# wifi-ra02.net
KiCad netlist of a schematic drawn in EasyEDA
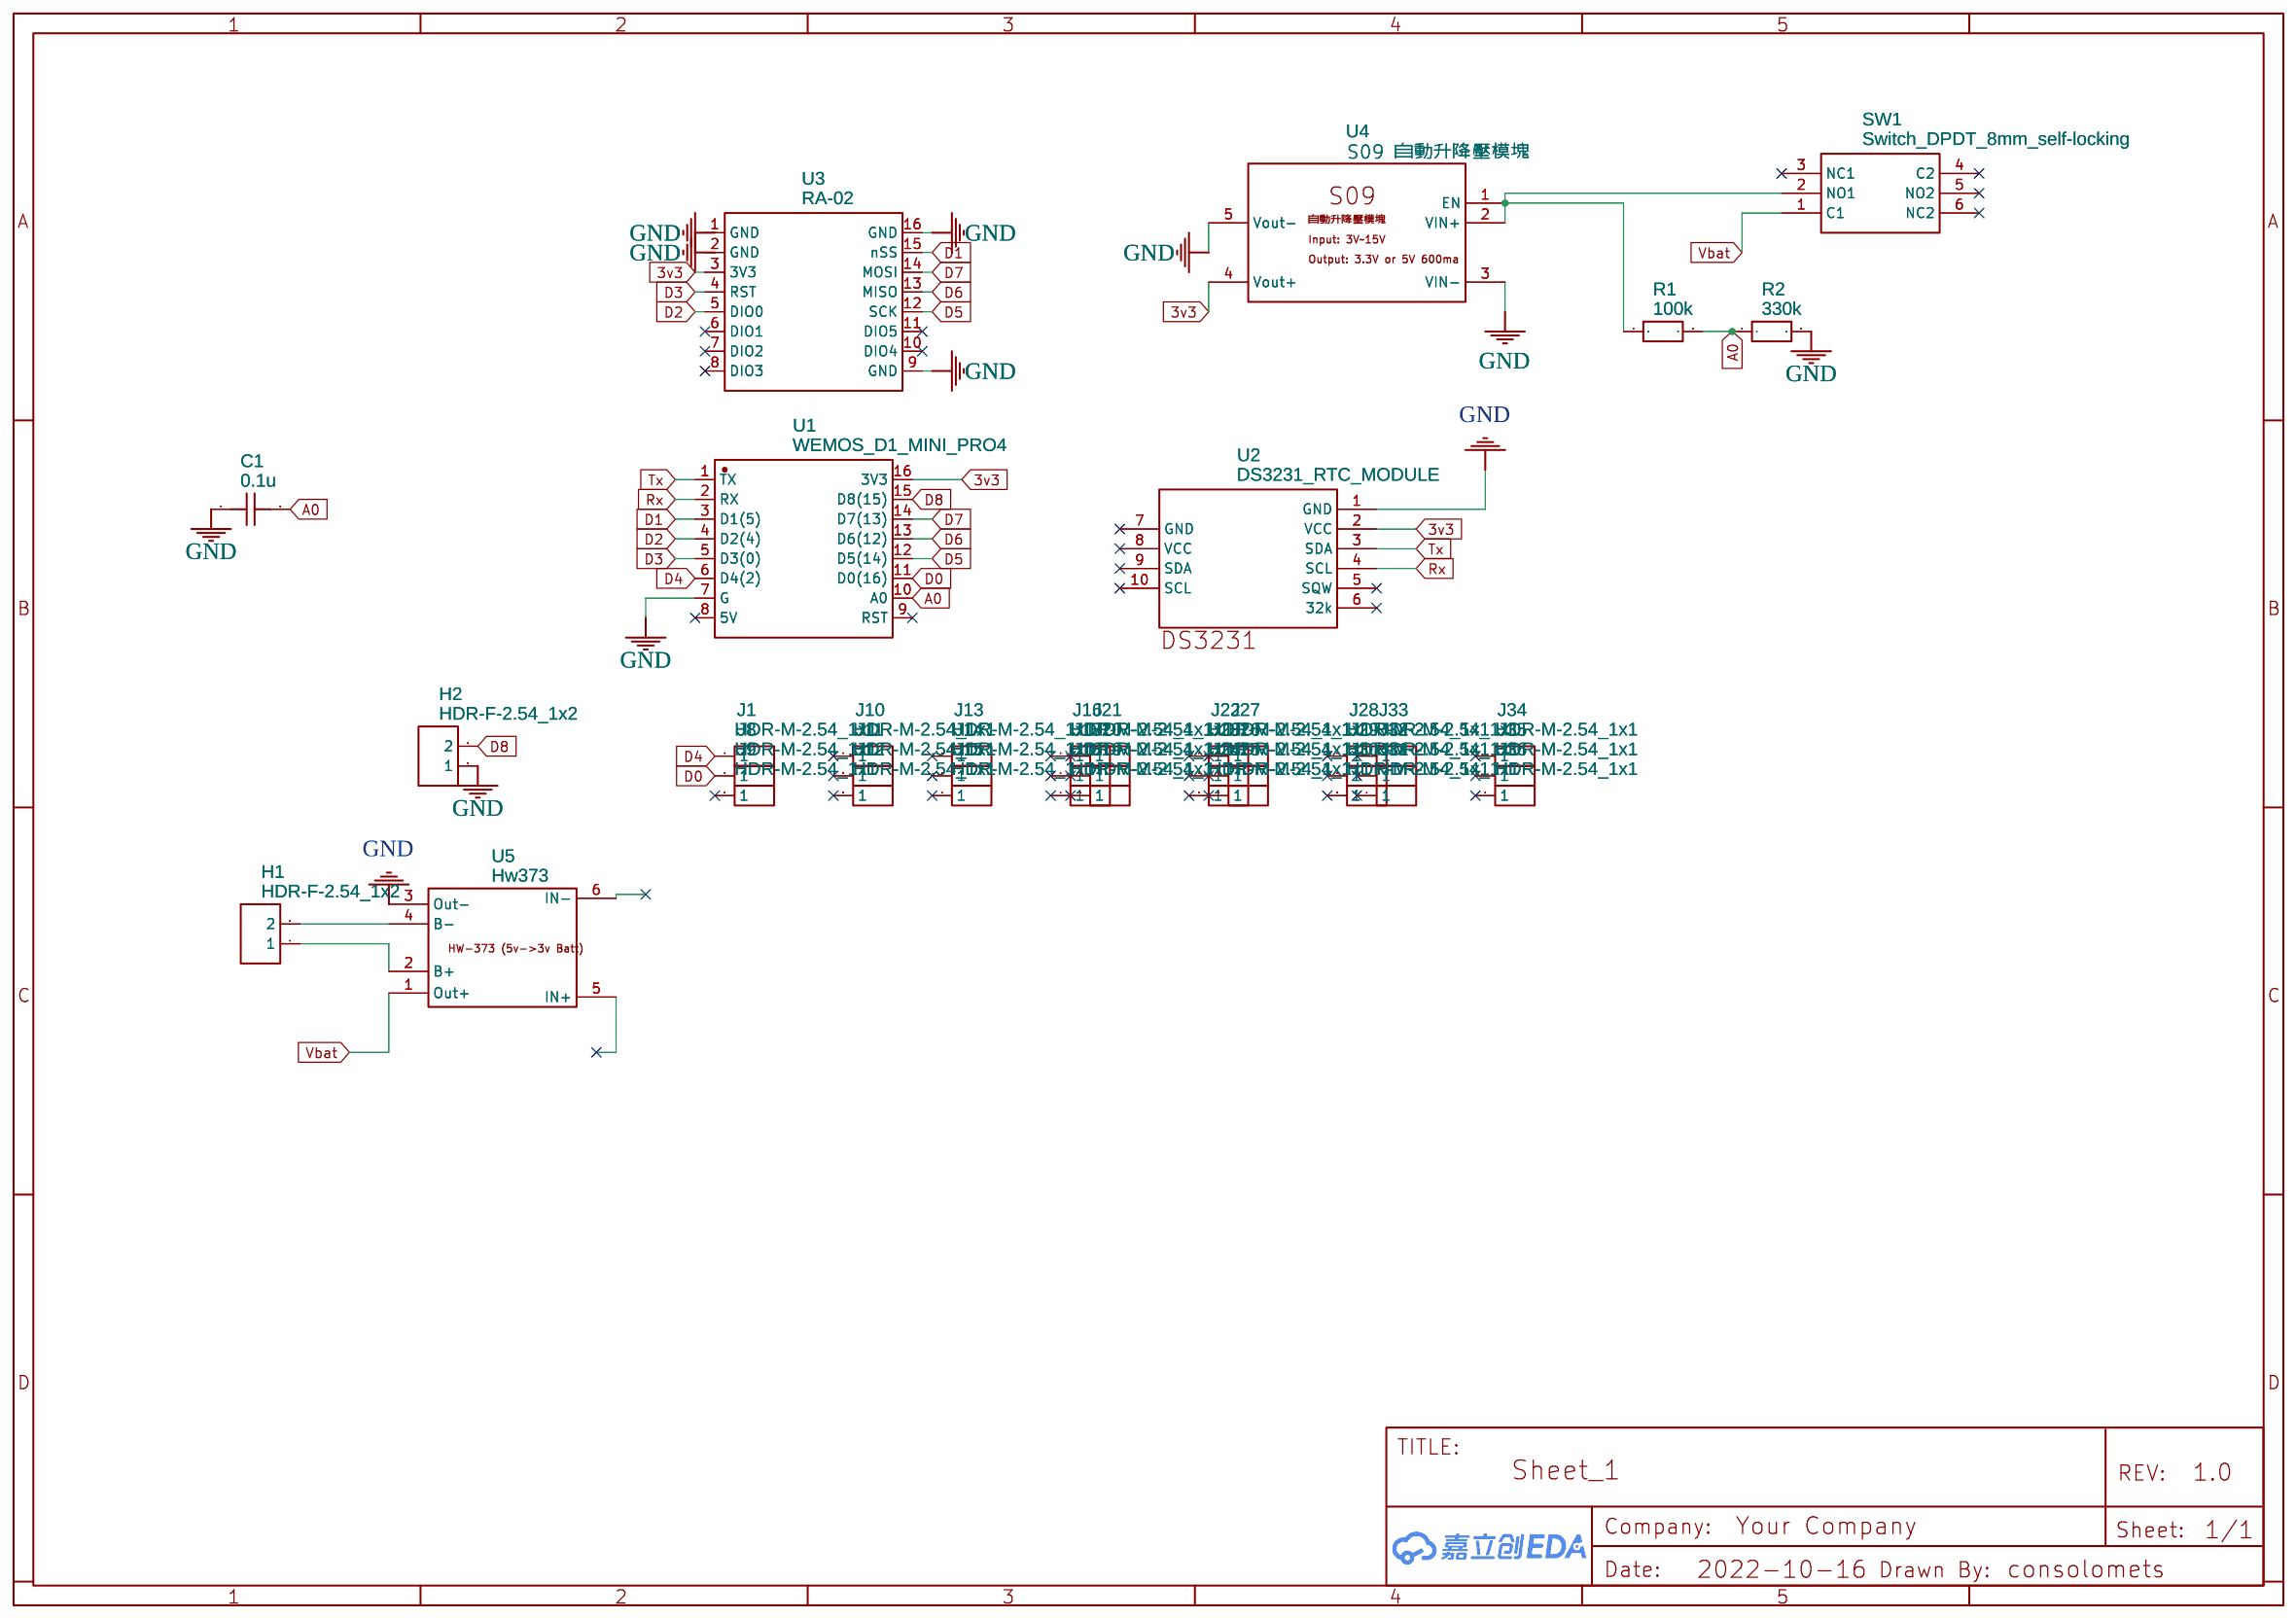
[diagram p0: schematic sheet]

(export (version "E")
  (design (tool "Eeschema 10.0.6"))
  (components
    (comp (ref "C1") (value "0.1u") (libsource (lib "") (part "C_0603_US")))
    (comp (ref "H1")
      (value "HDR-F-2.54_1x2")
      (fields (field (name "BOM_Supplier Part") "C49661"))
      (libsource (lib "") (part "HDR-F-2.54_1x2"))
    )
    (comp (ref "H2")
      (value "HDR-F-2.54_1x2")
      (fields (field (name "BOM_Supplier Part") "C49661"))
      (libsource (lib "") (part "HDR-F-2.54_1x2"))
    )
    (comp (ref "J1")
      (value "HDR-M-2.54_1x1")
      (fields (field (name "BOM_Supplier Part") "C81276"))
      (libsource (lib "") (part "HDR-M-2.54_1x1"))
    )
    (comp (ref "J8")
      (value "HDR-M-2.54_1x1")
      (fields (field (name "BOM_Supplier Part") "C81276"))
      (libsource (lib "") (part "HDR-M-2.54_1x1"))
    )
    (comp (ref "J9")
      (value "HDR-M-2.54_1x1")
      (fields (field (name "BOM_Supplier Part") "C81276"))
      (libsource (lib "") (part "HDR-M-2.54_1x1"))
    )
    (comp (ref "J10")
      (value "HDR-M-2.54_1x1")
      (fields (field (name "BOM_Supplier Part") "C81276"))
      (libsource (lib "") (part "HDR-M-2.54_1x1"))
    )
    (comp (ref "J11")
      (value "HDR-M-2.54_1x1")
      (fields (field (name "BOM_Supplier Part") "C81276"))
      (libsource (lib "") (part "HDR-M-2.54_1x1"))
    )
    (comp (ref "J12")
      (value "HDR-M-2.54_1x1")
      (fields (field (name "BOM_Supplier Part") "C81276"))
      (libsource (lib "") (part "HDR-M-2.54_1x1"))
    )
    (comp (ref "J13")
      (value "HDR-M-2.54_1x1")
      (fields (field (name "BOM_Supplier Part") "C81276"))
      (libsource (lib "") (part "HDR-M-2.54_1x1"))
    )
    (comp (ref "J14")
      (value "HDR-M-2.54_1x1")
      (fields (field (name "BOM_Supplier Part") "C81276"))
      (libsource (lib "") (part "HDR-M-2.54_1x1"))
    )
    (comp (ref "J15")
      (value "HDR-M-2.54_1x1")
      (fields (field (name "BOM_Supplier Part") "C81276"))
      (libsource (lib "") (part "HDR-M-2.54_1x1"))
    )
    (comp (ref "J16")
      (value "HDR-M-2.54_1x1")
      (fields (field (name "BOM_Supplier Part") "C81276"))
      (libsource (lib "") (part "HDR-M-2.54_1x1"))
    )
    (comp (ref "J17")
      (value "HDR-M-2.54_1x1")
      (fields (field (name "BOM_Supplier Part") "C81276"))
      (libsource (lib "") (part "HDR-M-2.54_1x1"))
    )
    (comp (ref "J18")
      (value "HDR-M-2.54_1x1")
      (fields (field (name "BOM_Supplier Part") "C81276"))
      (libsource (lib "") (part "HDR-M-2.54_1x1"))
    )
    (comp (ref "J19")
      (value "HDR-M-2.54_1x1")
      (fields (field (name "BOM_Supplier Part") "C81276"))
      (libsource (lib "") (part "HDR-M-2.54_1x1"))
    )
    (comp (ref "J20")
      (value "HDR-M-2.54_1x1")
      (fields (field (name "BOM_Supplier Part") "C81276"))
      (libsource (lib "") (part "HDR-M-2.54_1x1"))
    )
    (comp (ref "J21")
      (value "HDR-M-2.54_1x1")
      (fields (field (name "BOM_Supplier Part") "C81276"))
      (libsource (lib "") (part "HDR-M-2.54_1x1"))
    )
    (comp (ref "J22")
      (value "HDR-M-2.54_1x1")
      (fields (field (name "BOM_Supplier Part") "C81276"))
      (libsource (lib "") (part "HDR-M-2.54_1x1"))
    )
    (comp (ref "J23")
      (value "HDR-M-2.54_1x1")
      (fields (field (name "BOM_Supplier Part") "C81276"))
      (libsource (lib "") (part "HDR-M-2.54_1x1"))
    )
    (comp (ref "J24")
      (value "HDR-M-2.54_1x1")
      (fields (field (name "BOM_Supplier Part") "C81276"))
      (libsource (lib "") (part "HDR-M-2.54_1x1"))
    )
    (comp (ref "J25")
      (value "HDR-M-2.54_1x1")
      (fields (field (name "BOM_Supplier Part") "C81276"))
      (libsource (lib "") (part "HDR-M-2.54_1x1"))
    )
    (comp (ref "J26")
      (value "HDR-M-2.54_1x1")
      (fields (field (name "BOM_Supplier Part") "C81276"))
      (libsource (lib "") (part "HDR-M-2.54_1x1"))
    )
    (comp (ref "J27")
      (value "HDR-M-2.54_1x1")
      (fields (field (name "BOM_Supplier Part") "C81276"))
      (libsource (lib "") (part "HDR-M-2.54_1x1"))
    )
    (comp (ref "J28")
      (value "HDR-M-2.54_1x1")
      (fields (field (name "BOM_Supplier Part") "C81276"))
      (libsource (lib "") (part "HDR-M-2.54_1x1"))
    )
    (comp (ref "J29")
      (value "HDR-M-2.54_1x1")
      (fields (field (name "BOM_Supplier Part") "C81276"))
      (libsource (lib "") (part "HDR-M-2.54_1x1"))
    )
    (comp (ref "J30")
      (value "HDR-M-2.54_1x1")
      (fields (field (name "BOM_Supplier Part") "C81276"))
      (libsource (lib "") (part "HDR-M-2.54_1x1"))
    )
    (comp (ref "J31")
      (value "HDR-M-2.54_1x1")
      (fields (field (name "BOM_Supplier Part") "C81276"))
      (libsource (lib "") (part "HDR-M-2.54_1x1"))
    )
    (comp (ref "J32")
      (value "HDR-M-2.54_1x1")
      (fields (field (name "BOM_Supplier Part") "C81276"))
      (libsource (lib "") (part "HDR-M-2.54_1x1"))
    )
    (comp (ref "J33")
      (value "HDR-M-2.54_1x1")
      (fields (field (name "BOM_Supplier Part") "C81276"))
      (libsource (lib "") (part "HDR-M-2.54_1x1"))
    )
    (comp (ref "J34")
      (value "HDR-M-2.54_1x1")
      (fields (field (name "BOM_Supplier Part") "C81276"))
      (libsource (lib "") (part "HDR-M-2.54_1x1"))
    )
    (comp (ref "J35")
      (value "HDR-M-2.54_1x1")
      (fields (field (name "BOM_Supplier Part") "C81276"))
      (libsource (lib "") (part "HDR-M-2.54_1x1"))
    )
    (comp (ref "J36")
      (value "HDR-M-2.54_1x1")
      (fields (field (name "BOM_Supplier Part") "C81276"))
      (libsource (lib "") (part "HDR-M-2.54_1x1"))
    )
    (comp (ref "R1") (value "100k") (libsource (lib "") (part "R_0603_EU")))
    (comp (ref "R2") (value "330k") (libsource (lib "") (part "R_0603_EU")))
    (comp (ref "SW1")
      (value "Switch_DPDT_8mm_self-locking")
      (libsource (lib "") (part "Switch_DPDT_8mm_self-locking"))
    )
    (comp (ref "U1")
      (value "WEMOS_D1_MINI_PRO4")
      (fields
        (field (name "BOM_Manufacturer Part") "Wemos_D1_mini_Pro4")
        (field (name "BOM_Supplier Part") "C2837266")
      )
      (libsource (lib "") (part "WEMOS_D1_MINI_PRO4"))
    )
    (comp (ref "U2")
      (value "DS3231_RTC_MODULE")
      (fields (field (name "BOM_Manufacturer Part") "DS3231"))
      (libsource (lib "") (part "DS3231_RTC_MODULE"))
    )
    (comp (ref "U3") (value "RA-02") (libsource (lib "") (part "RA-02")))
    (comp (ref "U4")
      (value "S09 自動升降壓模塊")
      (fields (field (name "BOM_Manufacturer Part") "S09"))
      (libsource (lib "") (part "S09 自動升降壓模塊"))
    )
    (comp (ref "U5")
      (value "Hw373")
      (fields (field (name "BOM_Manufacturer Part") "HW-373"))
      (libsource (lib "") (part "Hw373"))
    )
  )
  (nets
    (net (code "1") (name "3v3") (class "Default")
      (node (ref "U1") (pin "16") (pinfunction "3V3_16") (pintype "unspecified"))
      (node (ref "U2") (pin "2") (pinfunction "VCC_2") (pintype "unspecified"))
      (node (ref "U3") (pin "3") (pinfunction "3V3_3") (pintype "unspecified"))
      (node (ref "U4") (pin "4") (pinfunction "Vout+_4") (pintype "output"))
    )
    (net (code "2") (name "A0") (class "Default")
      (node (ref "C1") (pin "2") (pinfunction "2_2") (pintype "unspecified"))
      (node (ref "R1") (pin "2") (pinfunction "2_2") (pintype "unspecified"))
      (node (ref "R2") (pin "1") (pinfunction "1_1") (pintype "unspecified"))
      (node (ref "U1") (pin "10") (pinfunction "A0_10") (pintype "unspecified"))
    )
    (net (code "3") (name "D0") (class "Default")
      (node (ref "J8") (pin "1") (pinfunction "1_1") (pintype "input"))
      (node (ref "U1") (pin "11") (pinfunction "D0(16)_11") (pintype "unspecified"))
    )
    (net (code "4") (name "D1") (class "Default")
      (node (ref "U1") (pin "3") (pinfunction "D1(5)_3") (pintype "unspecified"))
      (node (ref "U3") (pin "15") (pinfunction "nSS_15") (pintype "unspecified"))
    )
    (net (code "5") (name "D2") (class "Default")
      (node (ref "U1") (pin "4") (pinfunction "D2(4)_4") (pintype "unspecified"))
      (node (ref "U3") (pin "5") (pinfunction "DIO0_5") (pintype "unspecified"))
    )
    (net (code "6") (name "D3") (class "Default")
      (node (ref "U1") (pin "5") (pinfunction "D3(0)_5") (pintype "unspecified"))
      (node (ref "U3") (pin "4") (pinfunction "RST_4") (pintype "unspecified"))
    )
    (net (code "7") (name "D4") (class "Default")
      (node (ref "J1") (pin "1") (pinfunction "1_1") (pintype "input"))
      (node (ref "U1") (pin "6") (pinfunction "D4(2)_6") (pintype "unspecified"))
    )
    (net (code "8") (name "D5") (class "Default")
      (node (ref "U1") (pin "12") (pinfunction "D5(14)_12") (pintype "unspecified"))
      (node (ref "U3") (pin "12") (pinfunction "SCK_12") (pintype "unspecified"))
    )
    (net (code "9") (name "D6") (class "Default")
      (node (ref "U1") (pin "13") (pinfunction "D6(12)_13") (pintype "unspecified"))
      (node (ref "U3") (pin "13") (pinfunction "MISO_13") (pintype "unspecified"))
    )
    (net (code "10") (name "D7") (class "Default")
      (node (ref "U1") (pin "14") (pinfunction "D7(13)_14") (pintype "unspecified"))
      (node (ref "U3") (pin "14") (pinfunction "MOSI_14") (pintype "unspecified"))
    )
    (net (code "11") (name "D8") (class "Default")
      (node (ref "H2") (pin "2") (pinfunction "2_2") (pintype "input"))
      (node (ref "U1") (pin "15") (pinfunction "D8(15)_15") (pintype "unspecified"))
    )
    (net (code "12") (name "GND") (class "Default")
      (node (ref "C1") (pin "1") (pinfunction "1_1") (pintype "unspecified"))
      (node (ref "H2") (pin "1") (pinfunction "1_1") (pintype "input"))
      (node (ref "R2") (pin "2") (pinfunction "2_2") (pintype "unspecified"))
      (node (ref "U1") (pin "7") (pinfunction "G_7") (pintype "unspecified"))
      (node (ref "U2") (pin "1") (pinfunction "GND_1") (pintype "unspecified"))
      (node (ref "U3") (pin "1") (pinfunction "GND_1") (pintype "unspecified"))
      (node (ref "U3") (pin "16") (pinfunction "GND_16") (pintype "unspecified"))
      (node (ref "U3") (pin "2") (pinfunction "GND_2") (pintype "unspecified"))
      (node (ref "U3") (pin "9") (pinfunction "GND_9") (pintype "unspecified"))
      (node (ref "U4") (pin "3") (pinfunction "VIN-_3") (pintype "passive"))
      (node (ref "U4") (pin "5") (pinfunction "Vout-_5") (pintype "output"))
      (node (ref "U5") (pin "3") (pinfunction "Out-_3") (pintype "unspecified"))
    )
    (net (code "13") (name "Net-(SW1-NO1)") (class "Default")
      (node (ref "R1") (pin "1") (pinfunction "1_1") (pintype "unspecified"))
      (node (ref "SW1") (pin "2") (pinfunction "NO1_2") (pintype "unspecified"))
      (node (ref "U4") (pin "1") (pinfunction "EN_1") (pintype "input"))
      (node (ref "U4") (pin "2") (pinfunction "VIN+_2") (pintype "passive"))
    )
    (net (code "14") (name "Net-(U5-B+)") (class "Default")
      (node (ref "H1") (pin "1") (pinfunction "1_1") (pintype "input"))
      (node (ref "U5") (pin "2") (pinfunction "B+_2") (pintype "passive"))
    )
    (net (code "15") (name "Net-(U5-B-)") (class "Default")
      (node (ref "H1") (pin "2") (pinfunction "2_2") (pintype "input"))
      (node (ref "U5") (pin "4") (pinfunction "B-_4") (pintype "unspecified"))
    )
    (net (code "16") (name "Rx") (class "Default")
      (node (ref "U1") (pin "2") (pinfunction "RX_2") (pintype "unspecified"))
      (node (ref "U2") (pin "4") (pinfunction "SCL_4") (pintype "unspecified"))
    )
    (net (code "17") (name "Tx") (class "Default")
      (node (ref "U1") (pin "1") (pinfunction "TX_1") (pintype "unspecified"))
      (node (ref "U2") (pin "3") (pinfunction "SDA_3") (pintype "unspecified"))
    )
    (net (code "18") (name "Vbat") (class "Default")
      (node (ref "SW1") (pin "1") (pinfunction "C1_1") (pintype "unspecified"))
      (node (ref "U5") (pin "1") (pinfunction "Out+_1") (pintype "output"))
    )
    (net (code "19") (name "unconnected-(J9-Pad1)") (class "Default")
      (node (ref "J9") (pin "1") (pinfunction "1_1") (pintype "input+no_connect"))
    )
    (net (code "20") (name "unconnected-(J10-Pad1)") (class "Default")
      (node (ref "J10") (pin "1") (pinfunction "1_1") (pintype "input+no_connect"))
    )
    (net (code "21") (name "unconnected-(J11-Pad1)") (class "Default")
      (node (ref "J11") (pin "1") (pinfunction "1_1") (pintype "input+no_connect"))
    )
    (net (code "22") (name "unconnected-(J12-Pad1)") (class "Default")
      (node (ref "J12") (pin "1") (pinfunction "1_1") (pintype "input+no_connect"))
    )
    (net (code "23") (name "unconnected-(J13-Pad1)") (class "Default")
      (node (ref "J13") (pin "1") (pinfunction "1_1") (pintype "input+no_connect"))
    )
    (net (code "24") (name "unconnected-(J14-Pad1)") (class "Default")
      (node (ref "J14") (pin "1") (pinfunction "1_1") (pintype "input+no_connect"))
    )
    (net (code "25") (name "unconnected-(J15-Pad1)") (class "Default")
      (node (ref "J15") (pin "1") (pinfunction "1_1") (pintype "input+no_connect"))
    )
    (net (code "26") (name "unconnected-(J16-Pad1)") (class "Default")
      (node (ref "J16") (pin "1") (pinfunction "1_1") (pintype "input+no_connect"))
    )
    (net (code "27") (name "unconnected-(J17-Pad1)") (class "Default")
      (node (ref "J17") (pin "1") (pinfunction "1_1") (pintype "input+no_connect"))
    )
    (net (code "28") (name "unconnected-(J18-Pad1)") (class "Default")
      (node (ref "J18") (pin "1") (pinfunction "1_1") (pintype "input+no_connect"))
    )
    (net (code "29") (name "unconnected-(J19-Pad1)") (class "Default")
      (node (ref "J19") (pin "1") (pinfunction "1_1") (pintype "input+no_connect"))
    )
    (net (code "30") (name "unconnected-(J20-Pad1)") (class "Default")
      (node (ref "J20") (pin "1") (pinfunction "1_1") (pintype "input+no_connect"))
    )
    (net (code "31") (name "unconnected-(J21-Pad1)") (class "Default")
      (node (ref "J21") (pin "1") (pinfunction "1_1") (pintype "input+no_connect"))
    )
    (net (code "32") (name "unconnected-(J22-Pad1)") (class "Default")
      (node (ref "J22") (pin "1") (pinfunction "1_1") (pintype "input+no_connect"))
    )
    (net (code "33") (name "unconnected-(J23-Pad1)") (class "Default")
      (node (ref "J23") (pin "1") (pinfunction "1_1") (pintype "input+no_connect"))
    )
    (net (code "34") (name "unconnected-(J24-Pad1)") (class "Default")
      (node (ref "J24") (pin "1") (pinfunction "1_1") (pintype "input+no_connect"))
    )
    (net (code "35") (name "unconnected-(J25-Pad1)") (class "Default")
      (node (ref "J25") (pin "1") (pinfunction "1_1") (pintype "input+no_connect"))
    )
    (net (code "36") (name "unconnected-(J26-Pad1)") (class "Default")
      (node (ref "J26") (pin "1") (pinfunction "1_1") (pintype "input+no_connect"))
    )
    (net (code "37") (name "unconnected-(J27-Pad1)") (class "Default")
      (node (ref "J27") (pin "1") (pinfunction "1_1") (pintype "input+no_connect"))
    )
    (net (code "38") (name "unconnected-(J28-Pad1)") (class "Default")
      (node (ref "J28") (pin "1") (pinfunction "1_1") (pintype "input+no_connect"))
    )
    (net (code "39") (name "unconnected-(J29-Pad1)") (class "Default")
      (node (ref "J29") (pin "1") (pinfunction "1_1") (pintype "input+no_connect"))
    )
    (net (code "40") (name "unconnected-(J30-Pad1)") (class "Default")
      (node (ref "J30") (pin "1") (pinfunction "1_1") (pintype "input+no_connect"))
    )
    (net (code "41") (name "unconnected-(J31-Pad1)") (class "Default")
      (node (ref "J31") (pin "1") (pinfunction "1_1") (pintype "input+no_connect"))
    )
    (net (code "42") (name "unconnected-(J32-Pad1)") (class "Default")
      (node (ref "J32") (pin "1") (pinfunction "1_1") (pintype "input+no_connect"))
    )
    (net (code "43") (name "unconnected-(J33-Pad1)") (class "Default")
      (node (ref "J33") (pin "1") (pinfunction "1_1") (pintype "input+no_connect"))
    )
    (net (code "44") (name "unconnected-(J34-Pad1)") (class "Default")
      (node (ref "J34") (pin "1") (pinfunction "1_1") (pintype "input+no_connect"))
    )
    (net (code "45") (name "unconnected-(J35-Pad1)") (class "Default")
      (node (ref "J35") (pin "1") (pinfunction "1_1") (pintype "input+no_connect"))
    )
    (net (code "46") (name "unconnected-(J36-Pad1)") (class "Default")
      (node (ref "J36") (pin "1") (pinfunction "1_1") (pintype "input+no_connect"))
    )
    (net (code "47") (name "unconnected-(SW1-C2-Pad4)") (class "Default")
      (node (ref "SW1") (pin "4") (pinfunction "C2_4") (pintype "unspecified+no_connect"))
    )
    (net (code "48") (name "unconnected-(SW1-NC1-Pad3)") (class "Default")
      (node (ref "SW1") (pin "3") (pinfunction "NC1_3") (pintype "unspecified+no_connect"))
    )
    (net (code "49") (name "unconnected-(SW1-NC2-Pad6)") (class "Default")
      (node (ref "SW1") (pin "6") (pinfunction "NC2_6") (pintype "unspecified+no_connect"))
    )
    (net (code "50") (name "unconnected-(SW1-NO2-Pad5)") (class "Default")
      (node (ref "SW1") (pin "5") (pinfunction "NO2_5") (pintype "unspecified+no_connect"))
    )
    (net (code "51") (name "unconnected-(U1-5V-Pad8)") (class "Default")
      (node (ref "U1") (pin "8") (pinfunction "5V_8") (pintype "unspecified+no_connect"))
    )
    (net (code "52") (name "unconnected-(U1-RST-Pad9)") (class "Default")
      (node (ref "U1") (pin "9") (pinfunction "RST_9") (pintype "unspecified+no_connect"))
    )
    (net (code "53") (name "unconnected-(U2-32k-Pad6)") (class "Default")
      (node (ref "U2") (pin "6") (pinfunction "32k_6") (pintype "unspecified+no_connect"))
    )
    (net (code "54") (name "unconnected-(U2-GND-Pad7)") (class "Default")
      (node (ref "U2") (pin "7") (pinfunction "GND_7") (pintype "unspecified+no_connect"))
    )
    (net (code "55") (name "unconnected-(U2-SCL-Pad10)") (class "Default")
      (node (ref "U2") (pin "10") (pinfunction "SCL_10") (pintype "unspecified+no_connect"))
    )
    (net (code "56") (name "unconnected-(U2-SDA-Pad9)") (class "Default")
      (node (ref "U2") (pin "9") (pinfunction "SDA_9") (pintype "unspecified+no_connect"))
    )
    (net (code "57") (name "unconnected-(U2-SQW-Pad5)") (class "Default")
      (node (ref "U2") (pin "5") (pinfunction "SQW_5") (pintype "unspecified+no_connect"))
    )
    (net (code "58") (name "unconnected-(U2-VCC-Pad8)") (class "Default")
      (node (ref "U2") (pin "8") (pinfunction "VCC_8") (pintype "unspecified+no_connect"))
    )
    (net (code "59") (name "unconnected-(U3-DIO1-Pad6)") (class "Default")
      (node (ref "U3") (pin "6") (pinfunction "DIO1_6") (pintype "unspecified+no_connect"))
    )
    (net (code "60") (name "unconnected-(U3-DIO2-Pad7)") (class "Default")
      (node (ref "U3") (pin "7") (pinfunction "DIO2_7") (pintype "unspecified+no_connect"))
    )
    (net (code "61") (name "unconnected-(U3-DIO3-Pad8)") (class "Default")
      (node (ref "U3") (pin "8") (pinfunction "DIO3_8") (pintype "unspecified+no_connect"))
    )
    (net (code "62") (name "unconnected-(U3-DIO4-Pad10)") (class "Default")
      (node (ref "U3") (pin "10") (pinfunction "DIO4_10") (pintype "unspecified+no_connect"))
    )
    (net (code "63") (name "unconnected-(U3-DIO5-Pad11)") (class "Default")
      (node (ref "U3") (pin "11") (pinfunction "DIO5_11") (pintype "unspecified+no_connect"))
    )
    (net (code "64") (name "unconnected-(U5-IN+-Pad5)") (class "Default")
      (node (ref "U5") (pin "5") (pinfunction "IN+_5") (pintype "unspecified+no_connect"))
    )
    (net (code "65") (name "unconnected-(U5-IN--Pad6)") (class "Default")
      (node (ref "U5") (pin "6") (pinfunction "IN-_6") (pintype "unspecified+no_connect"))
    )
  )
)
